# arm.net
KiCad netlist of a schematic drawn in Altium Designer
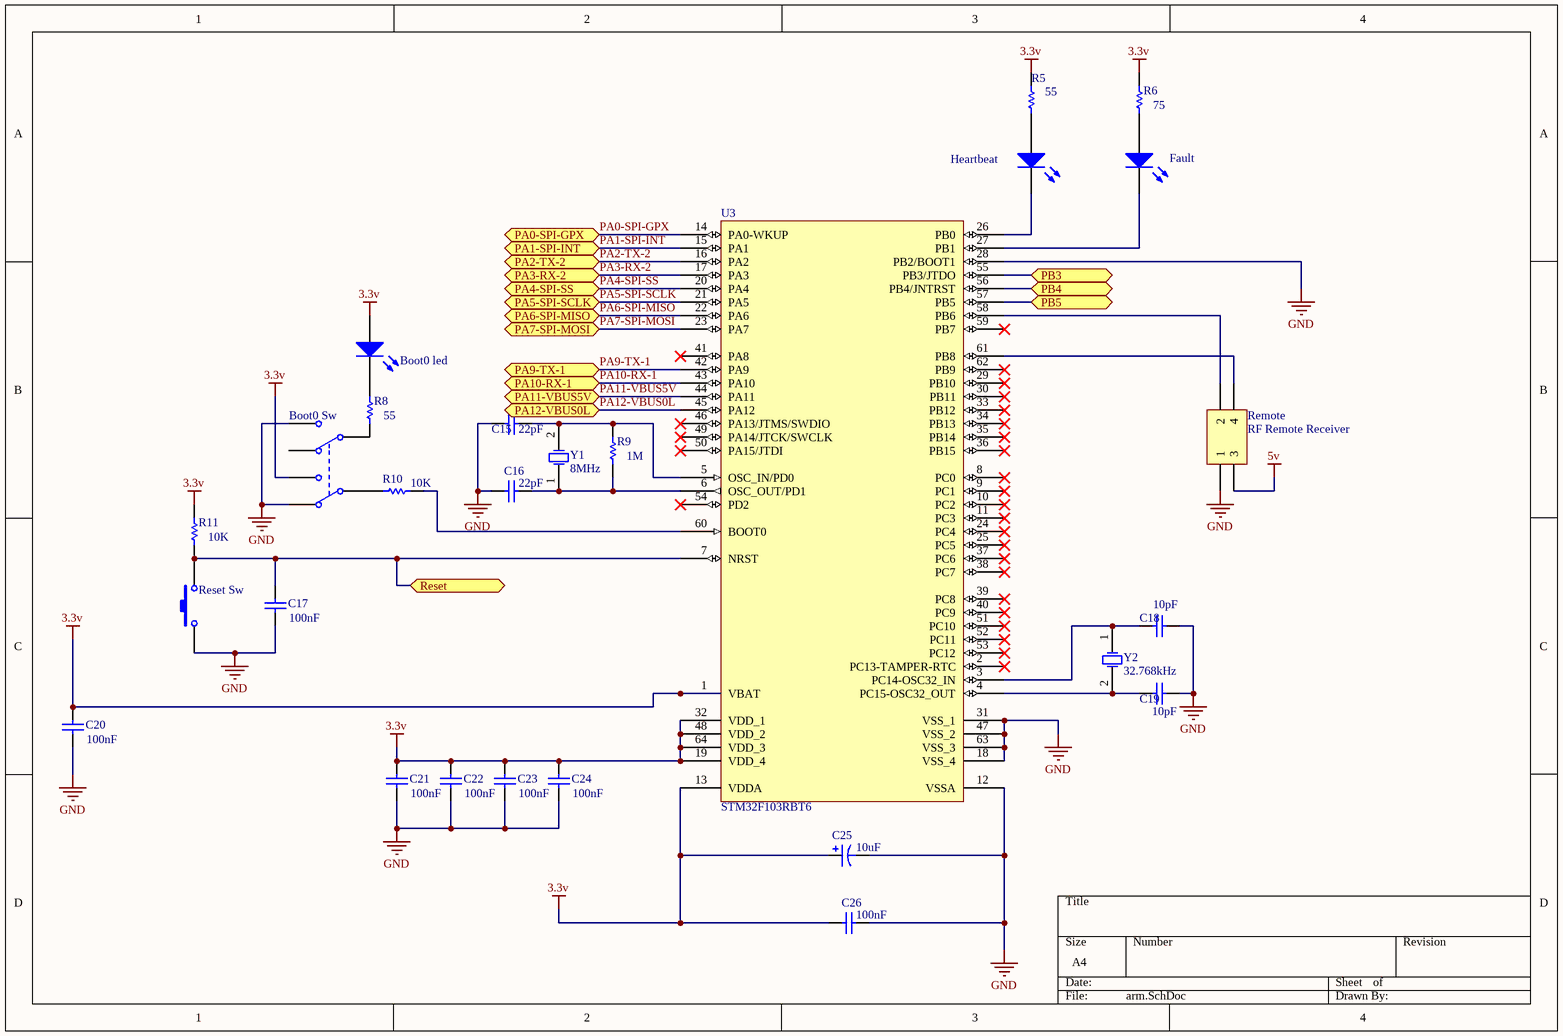
[diagram p0: arm.SchDoc]

(export (version "E")
  (design (tool "Eeschema 10.0.6"))
  (components
    (comp (ref "Boot0")
      (value "Boot0 led")
      (footprint "3.2X1.6X1.1")
      (description "Typical RED, GREEN, YELLOW, AMBER GaAs LED")
      (fields (field (name "PUBLISHER") "Altium Limited"))
      (libsource (lib "Miscellaneous Devices") (part "LED2"))
    )
    (comp (ref "Boot0 Sw")
      (value "BOOT0 SW")
      (footprint "Switch DPDT")
      (description "Switch")
      (fields (field (name "PUBLISHER") "Altium Limited"))
      (libsource (lib "Miscellaneous Devices") (part "SW DPDT"))
    )
    (comp (ref "C15")
      (value "22pF")
      (footprint "CAPC1608L")
      (description "Capacitor")
      (fields (field (name "Comment") "Cap") (field (name "PUBLISHER") "Altium Limited"))
      (libsource (lib "Miscellaneous Devices") (part "Cap"))
    )
    (comp (ref "C16")
      (value "22pF")
      (footprint "CAPC1608L")
      (description "Capacitor")
      (fields (field (name "Comment") "Cap") (field (name "PUBLISHER") "Altium Limited"))
      (libsource (lib "Miscellaneous Devices") (part "Cap"))
    )
    (comp (ref "C17")
      (value "100nF")
      (footprint "CAPC1608L")
      (description "Capacitor")
      (fields (field (name "Comment") "Cap") (field (name "PUBLISHER") "Altium Limited"))
      (libsource (lib "Miscellaneous Devices") (part "Cap"))
    )
    (comp (ref "C18")
      (value "10pF")
      (footprint "CAPC1608L")
      (description "Capacitor")
      (fields (field (name "Comment") "Cap") (field (name "PUBLISHER") "Altium Limited"))
      (libsource (lib "Miscellaneous Devices") (part "Cap"))
    )
    (comp (ref "C19")
      (value "10pF")
      (footprint "CAPC1608L")
      (description "Capacitor")
      (fields (field (name "Comment") "Cap") (field (name "PUBLISHER") "Altium Limited"))
      (libsource (lib "Miscellaneous Devices") (part "Cap"))
    )
    (comp (ref "C20")
      (value "100nF")
      (footprint "CAPC1608L")
      (description "Capacitor")
      (fields (field (name "Comment") "Cap") (field (name "PUBLISHER") "Altium Limited"))
      (libsource (lib "Miscellaneous Devices") (part "Cap"))
    )
    (comp (ref "C21")
      (value "100nF")
      (footprint "CAPC1608L")
      (description "Capacitor")
      (fields (field (name "Comment") "Cap") (field (name "PUBLISHER") "Altium Limited"))
      (libsource (lib "Miscellaneous Devices") (part "Cap"))
    )
    (comp (ref "C22")
      (value "100nF")
      (footprint "CAPC1608L")
      (description "Capacitor")
      (fields (field (name "Comment") "Cap") (field (name "PUBLISHER") "Altium Limited"))
      (libsource (lib "Miscellaneous Devices") (part "Cap"))
    )
    (comp (ref "C23")
      (value "100nF")
      (footprint "CAPC1608L")
      (description "Capacitor")
      (fields (field (name "Comment") "Cap") (field (name "PUBLISHER") "Altium Limited"))
      (libsource (lib "Miscellaneous Devices") (part "Cap"))
    )
    (comp (ref "C24")
      (value "100nF")
      (footprint "CAPC1608L")
      (description "Capacitor")
      (fields (field (name "Comment") "Cap") (field (name "PUBLISHER") "Altium Limited"))
      (libsource (lib "Miscellaneous Devices") (part "Cap"))
    )
    (comp (ref "C25")
      (value "10uF")
      (footprint "CAPC3216M")
      (description "Polarized Capacitor (Surface Mount)")
      (fields (field (name "Comment") "Cap Pol3") (field (name "PUBLISHER") "Altium Limited"))
      (libsource (lib "Miscellaneous Devices") (part "Cap Pol3"))
    )
    (comp (ref "C26")
      (value "100nF")
      (footprint "CAPC1608L")
      (description "Capacitor")
      (fields (field (name "Comment") "Cap") (field (name "PUBLISHER") "Altium Limited"))
      (libsource (lib "Miscellaneous Devices") (part "Cap"))
    )
    (comp (ref "Fault")
      (value "Fault LED")
      (footprint "3.2X1.6X1.1")
      (description "Typical RED, GREEN, YELLOW, AMBER GaAs LED")
      (fields (field (name "PUBLISHER") "Altium Limited"))
      (libsource (lib "Miscellaneous Devices") (part "LED2"))
    )
    (comp (ref "Heartbeat")
      (value "Heartbeat LED")
      (footprint "3.2X1.6X1.1")
      (description "Typical RED, GREEN, YELLOW, AMBER GaAs LED")
      (fields (field (name "PUBLISHER") "Altium Limited"))
      (libsource (lib "Miscellaneous Devices") (part "LED2"))
    )
    (comp (ref "R5")
      (value "55")
      (footprint "RESC1608L")
      (description "Resistor")
      (fields (field (name "Comment") "Res1") (field (name "PUBLISHER") "Altium Limited"))
      (libsource (lib "Miscellaneous Devices") (part "Res1"))
    )
    (comp (ref "R6")
      (value "75")
      (footprint "RESC1608L")
      (description "Resistor")
      (fields (field (name "Comment") "Res1") (field (name "PUBLISHER") "Altium Limited"))
      (libsource (lib "Miscellaneous Devices") (part "Res1"))
    )
    (comp (ref "R8")
      (value "55")
      (footprint "RESC1608L")
      (description "Resistor")
      (fields (field (name "Comment") "Res1") (field (name "PUBLISHER") "Altium Limited"))
      (libsource (lib "Miscellaneous Devices") (part "Res1"))
    )
    (comp (ref "R9")
      (value "1M")
      (footprint "RESC1608L")
      (description "Resistor")
      (fields (field (name "Comment") "Res1") (field (name "PUBLISHER") "Altium Limited"))
      (libsource (lib "Miscellaneous Devices") (part "Res1"))
    )
    (comp (ref "R10")
      (value "10K")
      (footprint "RESC1608L")
      (description "Resistor")
      (fields (field (name "Comment") "Res1") (field (name "PUBLISHER") "Altium Limited"))
      (libsource (lib "Miscellaneous Devices") (part "Res1"))
    )
    (comp (ref "R11")
      (value "10K")
      (footprint "RESC1608L")
      (description "Resistor")
      (fields (field (name "Comment") "Res1") (field (name "PUBLISHER") "Altium Limited"))
      (libsource (lib "Miscellaneous Devices") (part "Res1"))
    )
    (comp (ref "Remote")
      (value "RF Remote Receiver")
      (footprint "NES connector")
      (description "Header, 2-Pin, Dual row")
      (fields (field (name "PUBLISHER") "Altium Limited"))
      (libsource (lib "Miscellaneous Connectors") (part "Header 2X2"))
    )
    (comp (ref "Reset Sw")
      (value "RESET SW")
      (footprint "tackSwitch")
      (description "Switch")
      (fields (field (name "PUBLISHER") "Altium Limited"))
      (libsource (lib "Miscellaneous Devices") (part "SW-PB"))
    )
    (comp (ref "U3")
      (value "STM32F103RBT6")
      (footprint "LQFP64_N")
      (description "STM32 ARM-based 32-bit MCU with 128 Kbytes Flash, 64-pin LQFP, Industrial Temperature")
      (fields (field (name "PUBLISHER") "Altium Limited"))
      (libsource (lib "ST Microcontroller 32-Bit STM32") (part "STM32F103RBT6"))
    )
    (comp (ref "Y1")
      (value "8MHz")
      (footprint "HC-49U")
      (description "Crystal Oscillator")
      (fields (field (name "PUBLISHER") "Altium Limited"))
      (libsource (lib "Miscellaneous Devices") (part "XTAL"))
    )
    (comp (ref "Y2")
      (value "32.768kHz")
      (footprint "R26")
      (description "Crystal Oscillator")
      (fields (field (name "PUBLISHER") "Altium Limited"))
      (libsource (lib "Miscellaneous Devices") (part "XTAL"))
    )
  )
  (nets
    (net (code "1") (name "/PA0-SPI-GPX") (class "Default")
      (node (ref "U3") (pin "14") (pinfunction "PA0-WKUP_14") (pintype "bidirectional"))
    )
    (net (code "2") (name "/PA1-SPI-INT") (class "Default")
      (node (ref "U3") (pin "15") (pinfunction "PA1_15") (pintype "bidirectional"))
    )
    (net (code "3") (name "/PA2-TX-2") (class "Default")
      (node (ref "U3") (pin "16") (pinfunction "PA2_16") (pintype "bidirectional"))
    )
    (net (code "4") (name "/PA3-RX-2") (class "Default")
      (node (ref "U3") (pin "17") (pinfunction "PA3_17") (pintype "bidirectional"))
    )
    (net (code "5") (name "/PA4-SPI-SS") (class "Default")
      (node (ref "U3") (pin "20") (pinfunction "PA4_20") (pintype "bidirectional"))
    )
    (net (code "6") (name "/PA5-SPI-SCLK") (class "Default")
      (node (ref "U3") (pin "21") (pinfunction "PA5_21") (pintype "bidirectional"))
    )
    (net (code "7") (name "/PA6-SPI-MISO") (class "Default")
      (node (ref "U3") (pin "22") (pinfunction "PA6_22") (pintype "bidirectional"))
    )
    (net (code "8") (name "/PA7-SPI-MOSI") (class "Default")
      (node (ref "U3") (pin "23") (pinfunction "PA7_23") (pintype "bidirectional"))
    )
    (net (code "9") (name "/PA9-TX-1") (class "Default")
      (node (ref "U3") (pin "42") (pinfunction "PA9_42") (pintype "bidirectional"))
    )
    (net (code "10") (name "/PA10-RX-1") (class "Default")
      (node (ref "U3") (pin "43") (pinfunction "PA10_43") (pintype "bidirectional"))
    )
    (net (code "11") (name "/PA11-VBUS5V") (class "Default")
      (node (ref "U3") (pin "44") (pinfunction "PA11_44") (pintype "bidirectional"))
    )
    (net (code "12") (name "/PA12-VBUS0L") (class "Default")
      (node (ref "U3") (pin "45") (pinfunction "PA12_45") (pintype "bidirectional"))
    )
    (net (code "13") (name "/PB3") (class "Default")
      (node (ref "U3") (pin "55") (pinfunction "PB3/JTDO_55") (pintype "bidirectional"))
    )
    (net (code "14") (name "/PB4") (class "Default")
      (node (ref "U3") (pin "56") (pinfunction "PB4/JNTRST_56") (pintype "bidirectional"))
    )
    (net (code "15") (name "/PB5") (class "Default")
      (node (ref "U3") (pin "57") (pinfunction "PB5_57") (pintype "bidirectional"))
    )
    (net (code "16") (name "/Reset") (class "Default")
      (node (ref "C17") (pin "2") (pinfunction "2_2") (pintype "passive"))
      (node (ref "R11") (pin "1") (pinfunction "1_1") (pintype "passive"))
      (node (ref "Reset Sw") (pin "2") (pinfunction "2_2") (pintype "passive"))
      (node (ref "U3") (pin "7") (pinfunction "NRST_7") (pintype "bidirectional"))
    )
    (net (code "17") (name "3.3v") (class "Default")
      (node (ref "Boot0") (pin "1") (pinfunction "A_1") (pintype "passive"))
      (node (ref "Boot0 Sw") (pin "2") (pinfunction "NO1_2") (pintype "passive"))
      (node (ref "C20") (pin "2") (pinfunction "2_2") (pintype "passive"))
      (node (ref "C21") (pin "2") (pinfunction "2_2") (pintype "passive"))
      (node (ref "C22") (pin "2") (pinfunction "2_2") (pintype "passive"))
      (node (ref "C23") (pin "2") (pinfunction "2_2") (pintype "passive"))
      (node (ref "C24") (pin "2") (pinfunction "2_2") (pintype "passive"))
      (node (ref "C25") (pin "1") (pinfunction "1_1") (pintype "passive"))
      (node (ref "C26") (pin "1") (pinfunction "1_1") (pintype "passive"))
      (node (ref "R11") (pin "2") (pinfunction "2_2") (pintype "passive"))
      (node (ref "R5") (pin "2") (pinfunction "2_2") (pintype "passive"))
      (node (ref "R6") (pin "2") (pinfunction "2_2") (pintype "passive"))
      (node (ref "U3") (pin "1") (pinfunction "VBAT_1") (pintype "power_in"))
      (node (ref "U3") (pin "13") (pinfunction "VDDA_13") (pintype "power_in"))
      (node (ref "U3") (pin "19") (pinfunction "VDD_4_19") (pintype "power_in"))
      (node (ref "U3") (pin "32") (pinfunction "VDD_1_32") (pintype "power_in"))
      (node (ref "U3") (pin "48") (pinfunction "VDD_2_48") (pintype "power_in"))
      (node (ref "U3") (pin "64") (pinfunction "VDD_3_64") (pintype "power_in"))
    )
    (net (code "18") (name "5v") (class "Default")
      (node (ref "Remote") (pin "3") (pinfunction "3_3") (pintype "passive"))
    )
    (net (code "19") (name "GND") (class "Default")
      (node (ref "Boot0 Sw") (pin "1") (pinfunction "NC1_1") (pintype "passive"))
      (node (ref "Boot0 Sw") (pin "6") (pinfunction "NO2_6") (pintype "passive"))
      (node (ref "C15") (pin "1") (pinfunction "1_1") (pintype "passive"))
      (node (ref "C16") (pin "1") (pinfunction "1_1") (pintype "passive"))
      (node (ref "C17") (pin "1") (pinfunction "1_1") (pintype "passive"))
      (node (ref "C18") (pin "1") (pinfunction "1_1") (pintype "passive"))
      (node (ref "C19") (pin "1") (pinfunction "1_1") (pintype "passive"))
      (node (ref "C20") (pin "1") (pinfunction "1_1") (pintype "passive"))
      (node (ref "C21") (pin "1") (pinfunction "1_1") (pintype "passive"))
      (node (ref "C22") (pin "1") (pinfunction "1_1") (pintype "passive"))
      (node (ref "C23") (pin "1") (pinfunction "1_1") (pintype "passive"))
      (node (ref "C24") (pin "1") (pinfunction "1_1") (pintype "passive"))
      (node (ref "C25") (pin "2") (pinfunction "2_2") (pintype "passive"))
      (node (ref "C26") (pin "2") (pinfunction "2_2") (pintype "passive"))
      (node (ref "Remote") (pin "1") (pinfunction "1_1") (pintype "passive"))
      (node (ref "Reset Sw") (pin "1") (pinfunction "1_1") (pintype "passive"))
      (node (ref "U3") (pin "12") (pinfunction "VSSA_12") (pintype "power_in"))
      (node (ref "U3") (pin "18") (pinfunction "VSS_4_18") (pintype "power_in"))
      (node (ref "U3") (pin "28") (pinfunction "PB2/BOOT1_28") (pintype "bidirectional"))
      (node (ref "U3") (pin "31") (pinfunction "VSS_1_31") (pintype "power_in"))
      (node (ref "U3") (pin "47") (pinfunction "VSS_2_47") (pintype "power_in"))
      (node (ref "U3") (pin "63") (pinfunction "VSS_3_63") (pintype "power_in"))
    )
    (net (code "20") (name "Net-(Boot0 Sw-COMMON1)") (class "Default")
      (node (ref "Boot0 Sw") (pin "3") (pinfunction "COMMON1_3") (pintype "passive"))
      (node (ref "R10") (pin "1") (pinfunction "1_1") (pintype "passive"))
    )
    (net (code "21") (name "Net-(Boot0 Sw-COMMON2)") (class "Default")
      (node (ref "Boot0 Sw") (pin "4") (pinfunction "COMMON2_4") (pintype "passive"))
      (node (ref "R8") (pin "1") (pinfunction "1_1") (pintype "passive"))
    )
    (net (code "22") (name "Net-(Boot0-K)") (class "Default")
      (node (ref "Boot0") (pin "2") (pinfunction "K_2") (pintype "passive"))
      (node (ref "R8") (pin "2") (pinfunction "2_2") (pintype "passive"))
    )
    (net (code "23") (name "Net-(Fault-A)") (class "Default")
      (node (ref "Fault") (pin "1") (pinfunction "A_1") (pintype "passive"))
      (node (ref "R6") (pin "1") (pinfunction "1_1") (pintype "passive"))
    )
    (net (code "24") (name "Net-(Fault-K)") (class "Default")
      (node (ref "Fault") (pin "2") (pinfunction "K_2") (pintype "passive"))
      (node (ref "U3") (pin "27") (pinfunction "PB1_27") (pintype "bidirectional"))
    )
    (net (code "25") (name "Net-(Heartbeat-A)") (class "Default")
      (node (ref "Heartbeat") (pin "1") (pinfunction "A_1") (pintype "passive"))
      (node (ref "R5") (pin "1") (pinfunction "1_1") (pintype "passive"))
    )
    (net (code "26") (name "Net-(Heartbeat-K)") (class "Default")
      (node (ref "Heartbeat") (pin "2") (pinfunction "K_2") (pintype "passive"))
      (node (ref "U3") (pin "26") (pinfunction "PB0_26") (pintype "bidirectional"))
    )
    (net (code "27") (name "Net-(U3-BOOT0)") (class "Default")
      (node (ref "R10") (pin "2") (pinfunction "2_2") (pintype "passive"))
      (node (ref "U3") (pin "60") (pinfunction "BOOT0_60") (pintype "input"))
    )
    (net (code "28") (name "Net-(U3-OSC_IN{slash}PD0)") (class "Default")
      (node (ref "C15") (pin "2") (pinfunction "2_2") (pintype "passive"))
      (node (ref "R9") (pin "1") (pinfunction "1_1") (pintype "passive"))
      (node (ref "U3") (pin "5") (pinfunction "OSC_IN/PD0_5") (pintype "input"))
      (node (ref "Y1") (pin "2") (pinfunction "OSC2_2") (pintype "passive"))
    )
    (net (code "29") (name "Net-(U3-OSC_OUT{slash}PD1)") (class "Default")
      (node (ref "C16") (pin "2") (pinfunction "2_2") (pintype "passive"))
      (node (ref "R9") (pin "2") (pinfunction "2_2") (pintype "passive"))
      (node (ref "U3") (pin "6") (pinfunction "OSC_OUT/PD1_6") (pintype "output"))
      (node (ref "Y1") (pin "1") (pinfunction "OSC1_1") (pintype "passive"))
    )
    (net (code "30") (name "Net-(U3-PB6)") (class "Default")
      (node (ref "Remote") (pin "2") (pinfunction "2_2") (pintype "passive"))
      (node (ref "U3") (pin "58") (pinfunction "PB6_58") (pintype "bidirectional"))
    )
    (net (code "31") (name "Net-(U3-PB8)") (class "Default")
      (node (ref "Remote") (pin "4") (pinfunction "4_4") (pintype "passive"))
      (node (ref "U3") (pin "61") (pinfunction "PB8_61") (pintype "bidirectional"))
    )
    (net (code "32") (name "Net-(U3-PC14-OSC32_IN)") (class "Default")
      (node (ref "C18") (pin "2") (pinfunction "2_2") (pintype "passive"))
      (node (ref "U3") (pin "3") (pinfunction "PC14-OSC32_IN_3") (pintype "bidirectional"))
      (node (ref "Y2") (pin "1") (pinfunction "OSC1_1") (pintype "passive"))
    )
    (net (code "33") (name "Net-(U3-PC15-OSC32_OUT)") (class "Default")
      (node (ref "C19") (pin "2") (pinfunction "2_2") (pintype "passive"))
      (node (ref "U3") (pin "4") (pinfunction "PC15-OSC32_OUT_4") (pintype "bidirectional"))
      (node (ref "Y2") (pin "2") (pinfunction "OSC2_2") (pintype "passive"))
    )
    (net (code "34") (name "unconnected-(Boot0 Sw-NC2-Pad5)") (class "Default")
      (node (ref "Boot0 Sw") (pin "5") (pinfunction "NC2_5") (pintype "passive"))
    )
    (net (code "35") (name "unconnected-(U3-PA8-Pad41)") (class "Default")
      (node (ref "U3") (pin "41") (pinfunction "PA8_41") (pintype "bidirectional+no_connect"))
    )
    (net (code "36") (name "unconnected-(U3-PA13{slash}JTMS{slash}SWDIO-Pad46)") (class "Default")
      (node (ref "U3") (pin "46") (pinfunction "PA13/JTMS/SWDIO_46") (pintype "bidirectional+no_connect"))
    )
    (net (code "37") (name "unconnected-(U3-PA14{slash}JTCK{slash}SWCLK-Pad49)") (class "Default")
      (node (ref "U3") (pin "49") (pinfunction "PA14/JTCK/SWCLK_49") (pintype "bidirectional+no_connect"))
    )
    (net (code "38") (name "unconnected-(U3-PA15{slash}JTDI-Pad50)") (class "Default")
      (node (ref "U3") (pin "50") (pinfunction "PA15/JTDI_50") (pintype "bidirectional+no_connect"))
    )
    (net (code "39") (name "unconnected-(U3-PB7-Pad59)") (class "Default")
      (node (ref "U3") (pin "59") (pinfunction "PB7_59") (pintype "bidirectional+no_connect"))
    )
    (net (code "40") (name "unconnected-(U3-PB9-Pad62)") (class "Default")
      (node (ref "U3") (pin "62") (pinfunction "PB9_62") (pintype "bidirectional+no_connect"))
    )
    (net (code "41") (name "unconnected-(U3-PB10-Pad29)") (class "Default")
      (node (ref "U3") (pin "29") (pinfunction "PB10_29") (pintype "bidirectional+no_connect"))
    )
    (net (code "42") (name "unconnected-(U3-PB11-Pad30)") (class "Default")
      (node (ref "U3") (pin "30") (pinfunction "PB11_30") (pintype "bidirectional+no_connect"))
    )
    (net (code "43") (name "unconnected-(U3-PB12-Pad33)") (class "Default")
      (node (ref "U3") (pin "33") (pinfunction "PB12_33") (pintype "bidirectional+no_connect"))
    )
    (net (code "44") (name "unconnected-(U3-PB13-Pad34)") (class "Default")
      (node (ref "U3") (pin "34") (pinfunction "PB13_34") (pintype "bidirectional+no_connect"))
    )
    (net (code "45") (name "unconnected-(U3-PB14-Pad35)") (class "Default")
      (node (ref "U3") (pin "35") (pinfunction "PB14_35") (pintype "bidirectional+no_connect"))
    )
    (net (code "46") (name "unconnected-(U3-PB15-Pad36)") (class "Default")
      (node (ref "U3") (pin "36") (pinfunction "PB15_36") (pintype "bidirectional+no_connect"))
    )
    (net (code "47") (name "unconnected-(U3-PC0-Pad8)") (class "Default")
      (node (ref "U3") (pin "8") (pinfunction "PC0_8") (pintype "bidirectional+no_connect"))
    )
    (net (code "48") (name "unconnected-(U3-PC1-Pad9)") (class "Default")
      (node (ref "U3") (pin "9") (pinfunction "PC1_9") (pintype "bidirectional+no_connect"))
    )
    (net (code "49") (name "unconnected-(U3-PC2-Pad10)") (class "Default")
      (node (ref "U3") (pin "10") (pinfunction "PC2_10") (pintype "bidirectional+no_connect"))
    )
    (net (code "50") (name "unconnected-(U3-PC3-Pad11)") (class "Default")
      (node (ref "U3") (pin "11") (pinfunction "PC3_11") (pintype "bidirectional+no_connect"))
    )
    (net (code "51") (name "unconnected-(U3-PC4-Pad24)") (class "Default")
      (node (ref "U3") (pin "24") (pinfunction "PC4_24") (pintype "bidirectional+no_connect"))
    )
    (net (code "52") (name "unconnected-(U3-PC5-Pad25)") (class "Default")
      (node (ref "U3") (pin "25") (pinfunction "PC5_25") (pintype "bidirectional+no_connect"))
    )
    (net (code "53") (name "unconnected-(U3-PC6-Pad37)") (class "Default")
      (node (ref "U3") (pin "37") (pinfunction "PC6_37") (pintype "bidirectional+no_connect"))
    )
    (net (code "54") (name "unconnected-(U3-PC7-Pad38)") (class "Default")
      (node (ref "U3") (pin "38") (pinfunction "PC7_38") (pintype "bidirectional+no_connect"))
    )
    (net (code "55") (name "unconnected-(U3-PC8-Pad39)") (class "Default")
      (node (ref "U3") (pin "39") (pinfunction "PC8_39") (pintype "bidirectional+no_connect"))
    )
    (net (code "56") (name "unconnected-(U3-PC9-Pad40)") (class "Default")
      (node (ref "U3") (pin "40") (pinfunction "PC9_40") (pintype "bidirectional+no_connect"))
    )
    (net (code "57") (name "unconnected-(U3-PC10-Pad51)") (class "Default")
      (node (ref "U3") (pin "51") (pinfunction "PC10_51") (pintype "bidirectional+no_connect"))
    )
    (net (code "58") (name "unconnected-(U3-PC11-Pad52)") (class "Default")
      (node (ref "U3") (pin "52") (pinfunction "PC11_52") (pintype "bidirectional+no_connect"))
    )
    (net (code "59") (name "unconnected-(U3-PC12-Pad53)") (class "Default")
      (node (ref "U3") (pin "53") (pinfunction "PC12_53") (pintype "bidirectional+no_connect"))
    )
    (net (code "60") (name "unconnected-(U3-PC13-TAMPER-RTC-Pad2)") (class "Default")
      (node (ref "U3") (pin "2") (pinfunction "PC13-TAMPER-RTC_2") (pintype "bidirectional+no_connect"))
    )
    (net (code "61") (name "unconnected-(U3-PD2-Pad54)") (class "Default")
      (node (ref "U3") (pin "54") (pinfunction "PD2_54") (pintype "bidirectional+no_connect"))
    )
  )
)
